# SKEMA_ALAT_UKUR-2025.net
KiCad netlist of a schematic drawn in EAGLE
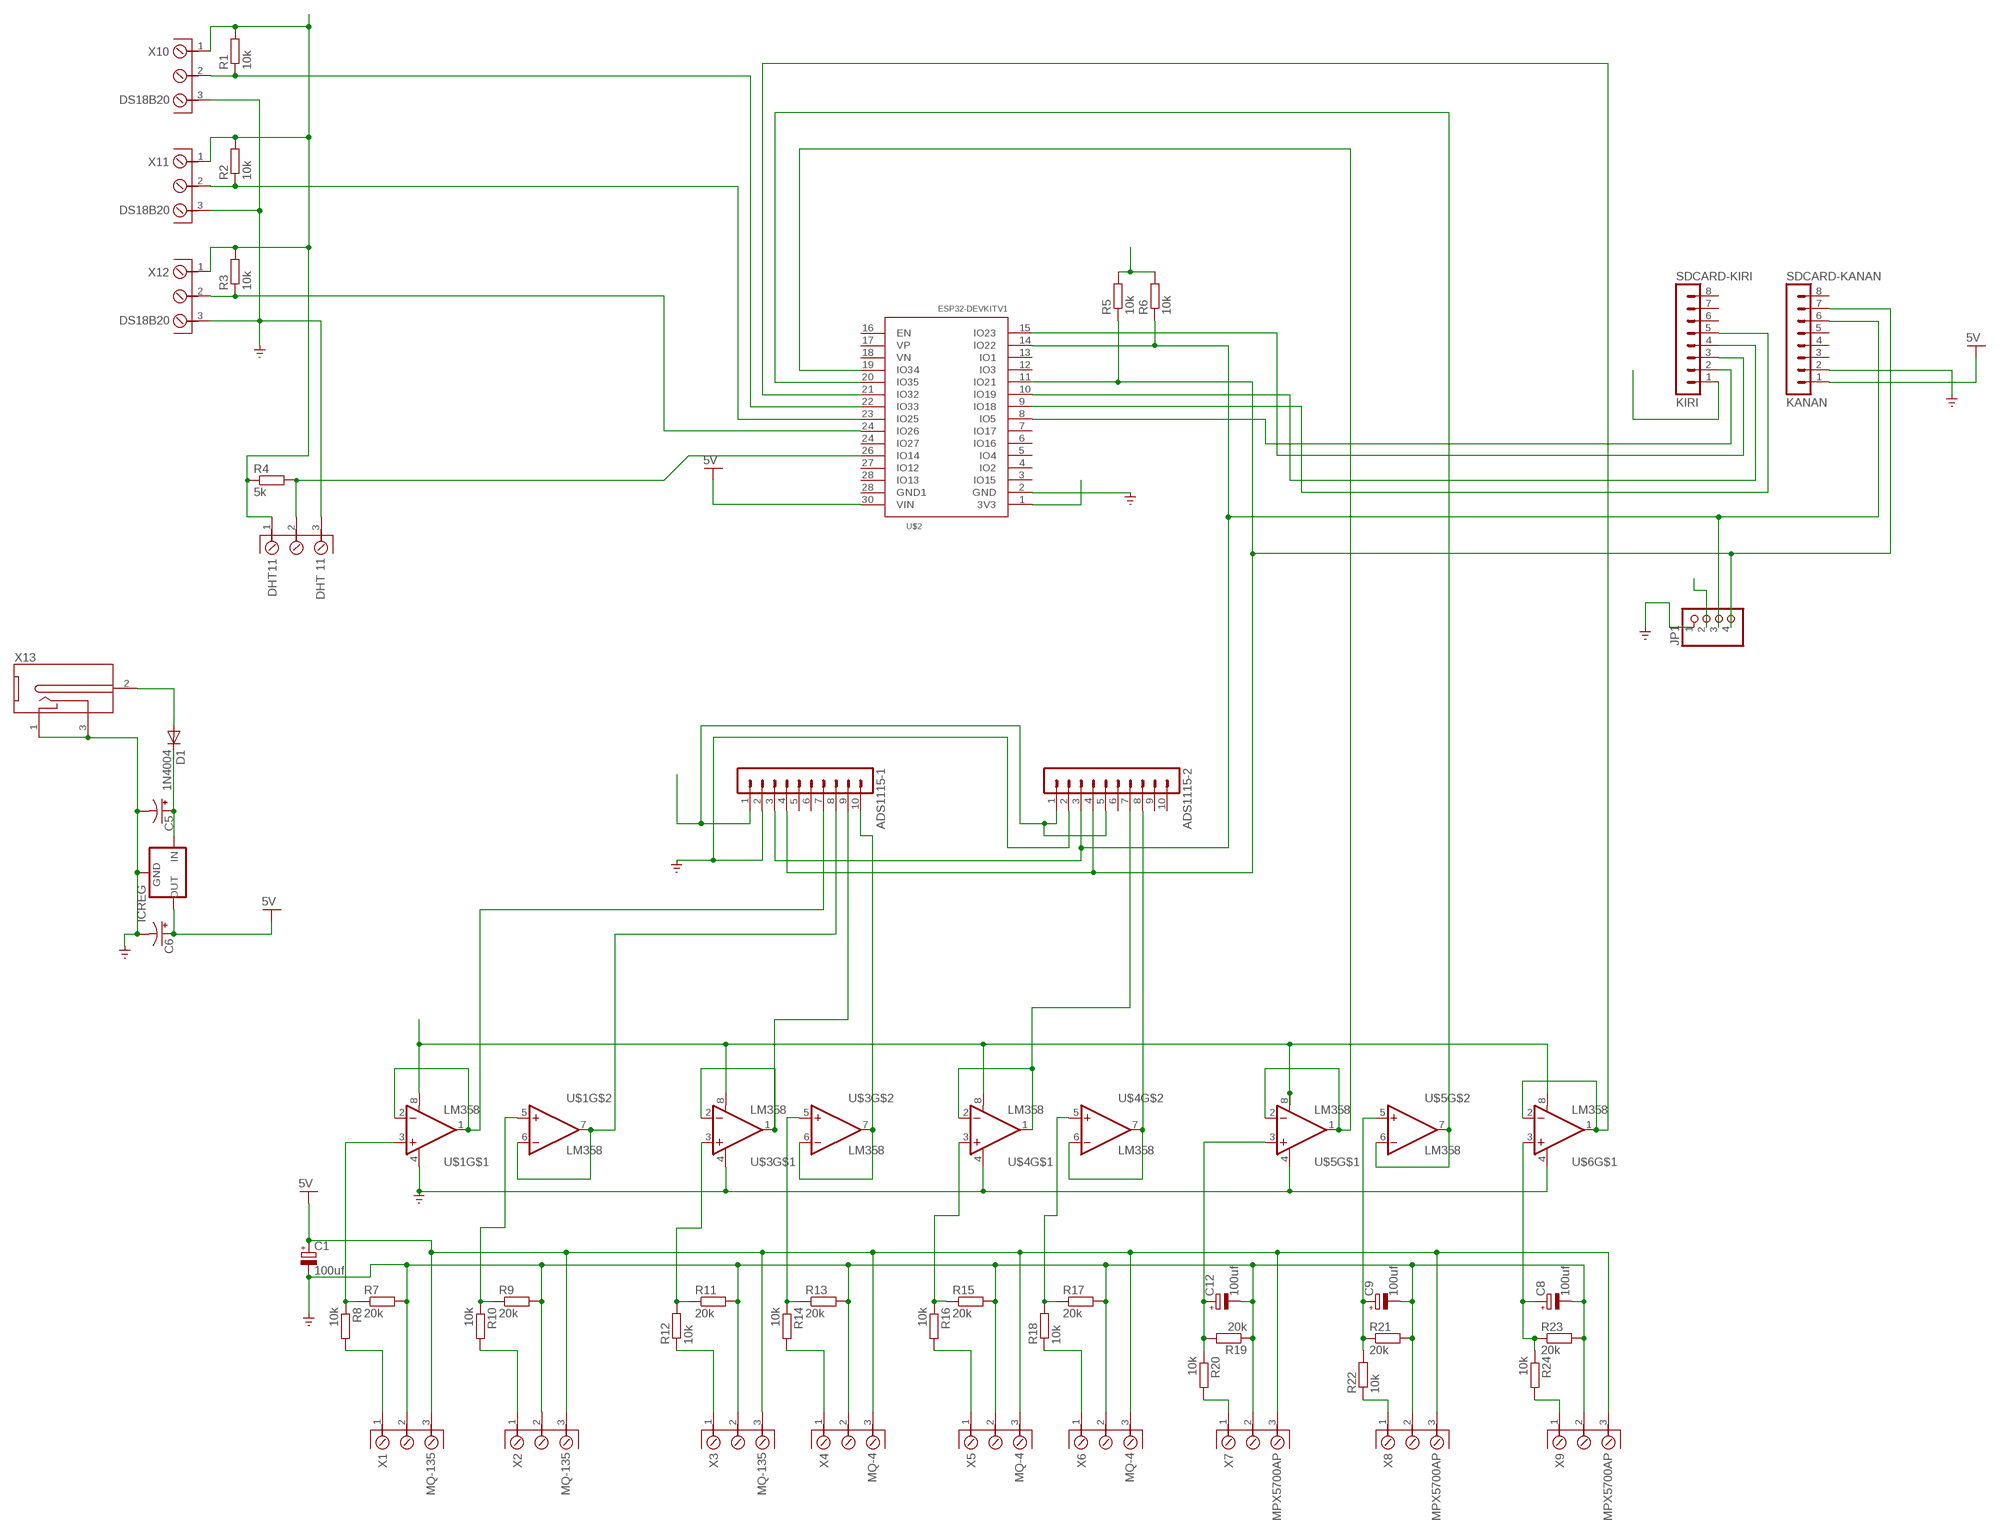
[diagram p0: schematic, sheet 1]

(export (version "E")
  (design (tool "Eeschema 10.0.6"))
  (components
    (comp (ref "ADS1115-1")
      (value "MA10-1")
      (footprint "eagle-import:MA10-1")
      (libsource (lib "eagle-import") (part "MA10-1"))
    )
    (comp (ref "ADS1115-2")
      (value "MA10-1")
      (footprint "eagle-import:MA10-1")
      (libsource (lib "eagle-import") (part "MA10-1"))
    )
    (comp (ref "C1")
      (value "100uf")
      (footprint "eagle-import:E5-10,5")
      (libsource (lib "eagle-import") (part "CPOL-EUE5-10.5"))
    )
    (comp (ref "C5")
      (value "CPOL-USE5-13")
      (footprint "eagle-import:E5-13")
      (libsource (lib "eagle-import") (part "CPOL-USE5-13"))
    )
    (comp (ref "C6")
      (value "CPOL-USE5-13")
      (footprint "eagle-import:E5-13")
      (libsource (lib "eagle-import") (part "CPOL-USE5-13"))
    )
    (comp (ref "C8")
      (value "100uf")
      (footprint "eagle-import:E5-10,5")
      (libsource (lib "eagle-import") (part "CPOL-EUE5-10.5"))
    )
    (comp (ref "C9")
      (value "100uf")
      (footprint "eagle-import:E5-10,5")
      (libsource (lib "eagle-import") (part "CPOL-EUE5-10.5"))
    )
    (comp (ref "C12")
      (value "100uf")
      (footprint "eagle-import:E5-10,5")
      (libsource (lib "eagle-import") (part "CPOL-EUE5-10.5"))
    )
    (comp (ref "D1")
      (value "1N4004")
      (footprint "eagle-import:DO41-10")
      (libsource (lib "eagle-import") (part "1N4004"))
    )
    (comp (ref "DHT11")
      (value "DHT 11")
      (footprint "eagle-import:AKL701_3_13")
      (libsource (lib "eagle-import") (part "AKL701_3_13"))
    )
    (comp (ref "ICREG")
      (value "78XXS")
      (footprint "eagle-import:78XXS")
      (libsource (lib "eagle-import") (part "78XXS"))
    )
    (comp (ref "JP1")
      (value "PINHD-1X4")
      (footprint "eagle-import:1X04")
      (libsource (lib "eagle-import") (part "PINHD-1X4"))
    )
    (comp (ref "R1")
      (value "10k")
      (footprint "eagle-import:0411_12")
      (libsource (lib "eagle-import") (part "R-EU_0411/12"))
    )
    (comp (ref "R2")
      (value "10k")
      (footprint "eagle-import:0411_12")
      (libsource (lib "eagle-import") (part "R-EU_0411/12"))
    )
    (comp (ref "R3")
      (value "10k")
      (footprint "eagle-import:0411_12")
      (libsource (lib "eagle-import") (part "R-EU_0411/12"))
    )
    (comp (ref "R4")
      (value "5k")
      (footprint "eagle-import:0411_12")
      (libsource (lib "eagle-import") (part "R-EU_0411/12"))
    )
    (comp (ref "R5")
      (value "10k")
      (footprint "eagle-import:0411_12")
      (libsource (lib "eagle-import") (part "R-EU_0411/12"))
    )
    (comp (ref "R6")
      (value "10k")
      (footprint "eagle-import:0411_12")
      (libsource (lib "eagle-import") (part "R-EU_0411/12"))
    )
    (comp (ref "R7")
      (value "20k")
      (footprint "eagle-import:0411_12")
      (libsource (lib "eagle-import") (part "R-EU_0411/12"))
    )
    (comp (ref "R8")
      (value "10k")
      (footprint "eagle-import:0411_12")
      (libsource (lib "eagle-import") (part "R-EU_0411/12"))
    )
    (comp (ref "R9")
      (value "20k")
      (footprint "eagle-import:0411_12")
      (libsource (lib "eagle-import") (part "R-EU_0411/12"))
    )
    (comp (ref "R10")
      (value "10k")
      (footprint "eagle-import:0411_12")
      (libsource (lib "eagle-import") (part "R-EU_0411/12"))
    )
    (comp (ref "R11")
      (value "20k")
      (footprint "eagle-import:0411_12")
      (libsource (lib "eagle-import") (part "R-EU_0411/12"))
    )
    (comp (ref "R12")
      (value "10k")
      (footprint "eagle-import:0411_12")
      (libsource (lib "eagle-import") (part "R-EU_0411/12"))
    )
    (comp (ref "R13")
      (value "20k")
      (footprint "eagle-import:0411_12")
      (libsource (lib "eagle-import") (part "R-EU_0411/12"))
    )
    (comp (ref "R14")
      (value "10k")
      (footprint "eagle-import:0411_12")
      (libsource (lib "eagle-import") (part "R-EU_0411/12"))
    )
    (comp (ref "R15")
      (value "20k")
      (footprint "eagle-import:0411_12")
      (libsource (lib "eagle-import") (part "R-EU_0411/12"))
    )
    (comp (ref "R16")
      (value "10k")
      (footprint "eagle-import:0411_12")
      (libsource (lib "eagle-import") (part "R-EU_0411/12"))
    )
    (comp (ref "R17")
      (value "20k")
      (footprint "eagle-import:0411_12")
      (libsource (lib "eagle-import") (part "R-EU_0411/12"))
    )
    (comp (ref "R18")
      (value "10k")
      (footprint "eagle-import:0411_12")
      (libsource (lib "eagle-import") (part "R-EU_0411/12"))
    )
    (comp (ref "R19")
      (value "20k")
      (footprint "eagle-import:0411_12")
      (libsource (lib "eagle-import") (part "R-EU_0411/12"))
    )
    (comp (ref "R20")
      (value "10k")
      (footprint "eagle-import:0411_12")
      (libsource (lib "eagle-import") (part "R-EU_0411/12"))
    )
    (comp (ref "R21")
      (value "20k")
      (footprint "eagle-import:0411_12")
      (libsource (lib "eagle-import") (part "R-EU_0411/12"))
    )
    (comp (ref "R22")
      (value "10k")
      (footprint "eagle-import:0411_12")
      (libsource (lib "eagle-import") (part "R-EU_0411/12"))
    )
    (comp (ref "R23")
      (value "20k")
      (footprint "eagle-import:0411_12")
      (libsource (lib "eagle-import") (part "R-EU_0411/12"))
    )
    (comp (ref "R24")
      (value "10k")
      (footprint "eagle-import:0411_12")
      (libsource (lib "eagle-import") (part "R-EU_0411/12"))
    )
    (comp (ref "SDCARD-KANAN")
      (value "KANAN")
      (footprint "eagle-import:MA08-1")
      (libsource (lib "eagle-import") (part "MA08-1"))
    )
    (comp (ref "SDCARD-KIRI")
      (value "KIRI")
      (footprint "eagle-import:MA08-1")
      (libsource (lib "eagle-import") (part "MA08-1"))
    )
    (comp (ref "U$1")
      (value "LM358")
      (footprint "eagle-import:DIP08")
      (libsource (lib "eagle-import") (part "LM358"))
    )
    (comp (ref "U$2")
      (value "ESP32DEVKITV1")
      (footprint "eagle-import:ESP32-DEVKITV1")
      (libsource (lib "eagle-import") (part "ESP32DEVKITV1"))
    )
    (comp (ref "U$3")
      (value "LM358")
      (footprint "eagle-import:DIP08")
      (libsource (lib "eagle-import") (part "LM358"))
    )
    (comp (ref "U$4")
      (value "LM358")
      (footprint "eagle-import:DIP08")
      (libsource (lib "eagle-import") (part "LM358"))
    )
    (comp (ref "U$5")
      (value "LM358")
      (footprint "eagle-import:DIP08")
      (libsource (lib "eagle-import") (part "LM358"))
    )
    (comp (ref "U$6")
      (value "LM358")
      (footprint "eagle-import:DIP08")
      (libsource (lib "eagle-import") (part "LM358"))
    )
    (comp (ref "X1")
      (value "MQ-135")
      (footprint "eagle-import:AKL701_3_13")
      (libsource (lib "eagle-import") (part "AKL701_3_13"))
    )
    (comp (ref "X2")
      (value "MQ-135")
      (footprint "eagle-import:AKL701_3_13")
      (libsource (lib "eagle-import") (part "AKL701_3_13"))
    )
    (comp (ref "X3")
      (value "MQ-135")
      (footprint "eagle-import:AKL701_3_13")
      (libsource (lib "eagle-import") (part "AKL701_3_13"))
    )
    (comp (ref "X4")
      (value "MQ-4")
      (footprint "eagle-import:AKL701_3_13")
      (libsource (lib "eagle-import") (part "AKL701_3_13"))
    )
    (comp (ref "X5")
      (value "MQ-4")
      (footprint "eagle-import:AKL701_3_13")
      (libsource (lib "eagle-import") (part "AKL701_3_13"))
    )
    (comp (ref "X6")
      (value "MQ-4")
      (footprint "eagle-import:AKL701_3_13")
      (libsource (lib "eagle-import") (part "AKL701_3_13"))
    )
    (comp (ref "X7")
      (value "MPX5700AP")
      (footprint "eagle-import:AKL701_3_13")
      (libsource (lib "eagle-import") (part "AKL701_3_13"))
    )
    (comp (ref "X8")
      (value "MPX5700AP")
      (footprint "eagle-import:AKL701_3_13")
      (libsource (lib "eagle-import") (part "AKL701_3_13"))
    )
    (comp (ref "X9")
      (value "MPX5700AP")
      (footprint "eagle-import:AKL701_3_13")
      (libsource (lib "eagle-import") (part "AKL701_3_13"))
    )
    (comp (ref "X10")
      (value "DS18B20")
      (footprint "eagle-import:AKL701_3_13")
      (libsource (lib "eagle-import") (part "AKL701_3_13"))
    )
    (comp (ref "X11")
      (value "DS18B20")
      (footprint "eagle-import:AKL701_3_13")
      (libsource (lib "eagle-import") (part "AKL701_3_13"))
    )
    (comp (ref "X12")
      (value "DS18B20")
      (footprint "eagle-import:AKL701_3_13")
      (libsource (lib "eagle-import") (part "AKL701_3_13"))
    )
    (comp (ref "X13")
      (value "DC-2.1MM-5MM")
      (footprint "eagle-import:DC-21MM")
      (libsource (lib "eagle-import") (part "DC-5MM-2.1MM"))
    )
  )
  (nets
    (net (code "1") (name "/3.3V") (class "Default")
      (node (ref "ADS1115-1") (pin "1") (pinfunction "1_1") (pintype "passive"))
      (node (ref "ADS1115-2") (pin "1") (pinfunction "1_1") (pintype "passive"))
      (node (ref "ADS1115-2") (pin "5") (pinfunction "5_5") (pintype "passive"))
      (node (ref "DHT11") (pin "1") (pinfunction "1_1") (pintype "passive"))
      (node (ref "JP1") (pin "2") (pinfunction "2_2") (pintype "passive"))
      (node (ref "R1") (pin "2") (pinfunction "2_2") (pintype "passive"))
      (node (ref "R2") (pin "2") (pinfunction "2_2") (pintype "passive"))
      (node (ref "R3") (pin "2") (pinfunction "2_2") (pintype "passive"))
      (node (ref "R4") (pin "1") (pinfunction "1_1") (pintype "passive"))
      (node (ref "R5") (pin "2") (pinfunction "2_2") (pintype "passive"))
      (node (ref "R6") (pin "2") (pinfunction "2_2") (pintype "passive"))
      (node (ref "SDCARD-KIRI") (pin "1") (pinfunction "1_1") (pintype "passive"))
      (node (ref "U$1") (pin "8") (pinfunction "V+_8") (pintype "power_in"))
      (node (ref "U$2") (pin "1") (pinfunction "3V3_1") (pintype "bidirectional"))
      (node (ref "U$3") (pin "8") (pinfunction "V+_8") (pintype "power_in"))
      (node (ref "U$4") (pin "8") (pinfunction "V+_8") (pintype "power_in"))
      (node (ref "U$5") (pin "8") (pinfunction "V+_8") (pintype "power_in"))
      (node (ref "U$6") (pin "8") (pinfunction "V+_8") (pintype "power_in"))
      (node (ref "X10") (pin "1") (pinfunction "1_1") (pintype "passive"))
      (node (ref "X11") (pin "1") (pinfunction "1_1") (pintype "passive"))
      (node (ref "X12") (pin "1") (pinfunction "1_1") (pintype "passive"))
    )
    (net (code "2") (name "5V") (class "Default")
      (node (ref "C1") (pin "+") (pinfunction "+_+") (pintype "passive"))
      (node (ref "C6") (pin "+") (pinfunction "+_+") (pintype "passive"))
      (node (ref "ICREG") (pin "OUT") (pinfunction "OUT_OUT") (pintype "passive"))
      (node (ref "SDCARD-KANAN") (pin "1") (pinfunction "1_1") (pintype "passive"))
      (node (ref "U$2") (pin "30") (pinfunction "VIN_30") (pintype "bidirectional"))
      (node (ref "X1") (pin "3") (pinfunction "3_3") (pintype "passive"))
      (node (ref "X2") (pin "3") (pinfunction "3_3") (pintype "passive"))
      (node (ref "X3") (pin "3") (pinfunction "3_3") (pintype "passive"))
      (node (ref "X4") (pin "3") (pinfunction "3_3") (pintype "passive"))
      (node (ref "X5") (pin "3") (pinfunction "3_3") (pintype "passive"))
      (node (ref "X6") (pin "3") (pinfunction "3_3") (pintype "passive"))
      (node (ref "X7") (pin "3") (pinfunction "3_3") (pintype "passive"))
      (node (ref "X8") (pin "3") (pinfunction "3_3") (pintype "passive"))
      (node (ref "X9") (pin "3") (pinfunction "3_3") (pintype "passive"))
    )
    (net (code "3") (name "GND_") (class "Default")
      (node (ref "ADS1115-1") (pin "2") (pinfunction "2_2") (pintype "passive"))
      (node (ref "ADS1115-2") (pin "2") (pinfunction "2_2") (pintype "passive"))
      (node (ref "C1") (pin "-") (pinfunction "-_-") (pintype "passive"))
      (node (ref "C12") (pin "-") (pinfunction "-_-") (pintype "passive"))
      (node (ref "C5") (pin "-") (pinfunction "-_-") (pintype "passive"))
      (node (ref "C6") (pin "-") (pinfunction "-_-") (pintype "passive"))
      (node (ref "C8") (pin "-") (pinfunction "-_-") (pintype "passive"))
      (node (ref "C9") (pin "-") (pinfunction "-_-") (pintype "passive"))
      (node (ref "DHT11") (pin "3") (pinfunction "3_3") (pintype "passive"))
      (node (ref "ICREG") (pin "GND") (pinfunction "GND_GND") (pintype "input"))
      (node (ref "JP1") (pin "1") (pinfunction "1_1") (pintype "passive"))
      (node (ref "R11") (pin "2") (pinfunction "2_2") (pintype "passive"))
      (node (ref "R13") (pin "2") (pinfunction "2_2") (pintype "passive"))
      (node (ref "R15") (pin "2") (pinfunction "2_2") (pintype "passive"))
      (node (ref "R17") (pin "2") (pinfunction "2_2") (pintype "passive"))
      (node (ref "R19") (pin "1") (pinfunction "1_1") (pintype "passive"))
      (node (ref "R21") (pin "2") (pinfunction "2_2") (pintype "passive"))
      (node (ref "R23") (pin "2") (pinfunction "2_2") (pintype "passive"))
      (node (ref "R7") (pin "2") (pinfunction "2_2") (pintype "passive"))
      (node (ref "R9") (pin "2") (pinfunction "2_2") (pintype "passive"))
      (node (ref "SDCARD-KANAN") (pin "2") (pinfunction "2_2") (pintype "passive"))
      (node (ref "U$1") (pin "4") (pinfunction "V-_4") (pintype "power_in"))
      (node (ref "U$2") (pin "2") (pinfunction "GND_2") (pintype "bidirectional"))
      (node (ref "U$3") (pin "4") (pinfunction "V-_4") (pintype "power_in"))
      (node (ref "U$4") (pin "4") (pinfunction "V-_4") (pintype "power_in"))
      (node (ref "U$5") (pin "4") (pinfunction "V-_4") (pintype "power_in"))
      (node (ref "U$6") (pin "4") (pinfunction "V-_4") (pintype "power_in"))
      (node (ref "X1") (pin "2") (pinfunction "2_2") (pintype "passive"))
      (node (ref "X10") (pin "3") (pinfunction "3_3") (pintype "passive"))
      (node (ref "X11") (pin "3") (pinfunction "3_3") (pintype "passive"))
      (node (ref "X12") (pin "3") (pinfunction "3_3") (pintype "passive"))
      (node (ref "X13") (pin "1") (pinfunction "1_1") (pintype "power_in"))
      (node (ref "X13") (pin "3") (pinfunction "2_3") (pintype "power_in"))
      (node (ref "X2") (pin "2") (pinfunction "2_2") (pintype "passive"))
      (node (ref "X3") (pin "2") (pinfunction "2_2") (pintype "passive"))
      (node (ref "X4") (pin "2") (pinfunction "2_2") (pintype "passive"))
      (node (ref "X5") (pin "2") (pinfunction "2_2") (pintype "passive"))
      (node (ref "X6") (pin "2") (pinfunction "2_2") (pintype "passive"))
      (node (ref "X7") (pin "2") (pinfunction "2_2") (pintype "passive"))
      (node (ref "X8") (pin "2") (pinfunction "2_2") (pintype "passive"))
      (node (ref "X9") (pin "2") (pinfunction "2_2") (pintype "passive"))
    )
    (net (code "4") (name "Net-(C5-Pad+)") (class "Default")
      (node (ref "C5") (pin "+") (pinfunction "+_+") (pintype "passive"))
      (node (ref "D1") (pin "C") (pinfunction "C_C") (pintype "passive"))
      (node (ref "ICREG") (pin "IN") (pinfunction "IN_IN") (pintype "input"))
    )
    (net (code "5") (name "Net-(R8-Pad2)") (class "Default")
      (node (ref "R8") (pin "2") (pinfunction "2_2") (pintype "passive"))
      (node (ref "X1") (pin "1") (pinfunction "1_1") (pintype "passive"))
    )
    (net (code "6") (name "Net-(R10-Pad2)") (class "Default")
      (node (ref "R10") (pin "2") (pinfunction "2_2") (pintype "passive"))
      (node (ref "X2") (pin "1") (pinfunction "1_1") (pintype "passive"))
    )
    (net (code "7") (name "Net-(R12-Pad1)") (class "Default")
      (node (ref "R12") (pin "1") (pinfunction "1_1") (pintype "passive"))
      (node (ref "X3") (pin "1") (pinfunction "1_1") (pintype "passive"))
    )
    (net (code "8") (name "Net-(R14-Pad2)") (class "Default")
      (node (ref "R14") (pin "2") (pinfunction "2_2") (pintype "passive"))
      (node (ref "X4") (pin "1") (pinfunction "1_1") (pintype "passive"))
    )
    (net (code "9") (name "Net-(R16-Pad2)") (class "Default")
      (node (ref "R16") (pin "2") (pinfunction "2_2") (pintype "passive"))
      (node (ref "X5") (pin "1") (pinfunction "1_1") (pintype "passive"))
    )
    (net (code "10") (name "Net-(R18-Pad1)") (class "Default")
      (node (ref "R18") (pin "1") (pinfunction "1_1") (pintype "passive"))
      (node (ref "X6") (pin "1") (pinfunction "1_1") (pintype "passive"))
    )
    (net (code "11") (name "Net-(R20-Pad2)") (class "Default")
      (node (ref "R20") (pin "2") (pinfunction "2_2") (pintype "passive"))
      (node (ref "X7") (pin "1") (pinfunction "1_1") (pintype "passive"))
    )
    (net (code "12") (name "Net-(R22-Pad1)") (class "Default")
      (node (ref "R22") (pin "1") (pinfunction "1_1") (pintype "passive"))
      (node (ref "X8") (pin "1") (pinfunction "1_1") (pintype "passive"))
    )
    (net (code "13") (name "Net-(R24-Pad2)") (class "Default")
      (node (ref "R24") (pin "2") (pinfunction "2_2") (pintype "passive"))
      (node (ref "X9") (pin "1") (pinfunction "1_1") (pintype "passive"))
    )
    (net (code "14") (name "Net-(U$1A-+IN)") (class "Default")
      (node (ref "R7") (pin "1") (pinfunction "1_1") (pintype "passive"))
      (node (ref "R8") (pin "1") (pinfunction "1_1") (pintype "passive"))
      (node (ref "U$1") (pin "3") (pinfunction "+IN_3") (pintype "input"))
    )
    (net (code "15") (name "Net-(U$1A--IN)") (class "Default")
      (node (ref "ADS1115-1") (pin "7") (pinfunction "7_7") (pintype "passive"))
      (node (ref "U$1") (pin "1") (pinfunction "OUT_1") (pintype "output"))
      (node (ref "U$1") (pin "2") (pinfunction "-IN_2") (pintype "input"))
    )
    (net (code "16") (name "Net-(U$1B-+IN)") (class "Default")
      (node (ref "R10") (pin "1") (pinfunction "1_1") (pintype "passive"))
      (node (ref "R9") (pin "1") (pinfunction "1_1") (pintype "passive"))
      (node (ref "U$1") (pin "5") (pinfunction "+IN_5") (pintype "input"))
    )
    (net (code "17") (name "Net-(U$1B--IN)") (class "Default")
      (node (ref "ADS1115-1") (pin "8") (pinfunction "8_8") (pintype "passive"))
      (node (ref "U$1") (pin "6") (pinfunction "-IN_6") (pintype "input"))
      (node (ref "U$1") (pin "7") (pinfunction "OUT_7") (pintype "output"))
    )
    (net (code "18") (name "Net-(U$2-IO5)") (class "Default")
      (node (ref "SDCARD-KIRI") (pin "2") (pinfunction "2_2") (pintype "passive"))
      (node (ref "U$2") (pin "8") (pinfunction "IO5_8") (pintype "bidirectional"))
    )
    (net (code "19") (name "Net-(U$2-IO14)") (class "Default")
      (node (ref "DHT11") (pin "2") (pinfunction "2_2") (pintype "passive"))
      (node (ref "R4") (pin "2") (pinfunction "2_2") (pintype "passive"))
      (node (ref "U$2") (pin "26") (pinfunction "IO14_26") (pintype "bidirectional"))
    )
    (net (code "20") (name "Net-(U$2-IO18)") (class "Default")
      (node (ref "SDCARD-KIRI") (pin "5") (pinfunction "5_5") (pintype "passive"))
      (node (ref "U$2") (pin "9") (pinfunction "IO18_9") (pintype "bidirectional"))
    )
    (net (code "21") (name "Net-(U$2-IO19)") (class "Default")
      (node (ref "SDCARD-KIRI") (pin "4") (pinfunction "4_4") (pintype "passive"))
      (node (ref "U$2") (pin "10") (pinfunction "IO19_10") (pintype "bidirectional"))
    )
    (net (code "22") (name "Net-(U$2-IO21)") (class "Default")
      (node (ref "ADS1115-1") (pin "4") (pinfunction "4_4") (pintype "passive"))
      (node (ref "ADS1115-2") (pin "4") (pinfunction "4_4") (pintype "passive"))
      (node (ref "JP1") (pin "4") (pinfunction "4_4") (pintype "passive"))
      (node (ref "R5") (pin "1") (pinfunction "1_1") (pintype "passive"))
      (node (ref "SDCARD-KANAN") (pin "7") (pinfunction "7_7") (pintype "passive"))
      (node (ref "U$2") (pin "11") (pinfunction "IO21_11") (pintype "bidirectional"))
    )
    (net (code "23") (name "Net-(U$2-IO22)") (class "Default")
      (node (ref "ADS1115-1") (pin "3") (pinfunction "3_3") (pintype "passive"))
      (node (ref "ADS1115-2") (pin "3") (pinfunction "3_3") (pintype "passive"))
      (node (ref "JP1") (pin "3") (pinfunction "3_3") (pintype "passive"))
      (node (ref "R6") (pin "1") (pinfunction "1_1") (pintype "passive"))
      (node (ref "SDCARD-KANAN") (pin "6") (pinfunction "6_6") (pintype "passive"))
      (node (ref "U$2") (pin "14") (pinfunction "IO22_14") (pintype "bidirectional"))
    )
    (net (code "24") (name "Net-(U$2-IO23)") (class "Default")
      (node (ref "SDCARD-KIRI") (pin "3") (pinfunction "3_3") (pintype "passive"))
      (node (ref "U$2") (pin "15") (pinfunction "IO23_15") (pintype "bidirectional"))
    )
    (net (code "25") (name "Net-(U$2-IO25)") (class "Default")
      (node (ref "R2") (pin "1") (pinfunction "1_1") (pintype "passive"))
      (node (ref "U$2") (pin "23") (pinfunction "IO25_23") (pintype "bidirectional"))
      (node (ref "X11") (pin "2") (pinfunction "2_2") (pintype "passive"))
    )
    (net (code "26") (name "Net-(U$2-IO26)") (class "Default")
      (node (ref "R3") (pin "1") (pinfunction "1_1") (pintype "passive"))
      (node (ref "U$2") (pin "24") (pinfunction "IO26_24") (pintype "bidirectional"))
      (node (ref "X12") (pin "2") (pinfunction "2_2") (pintype "passive"))
    )
    (net (code "27") (name "Net-(U$2-IO32)") (class "Default")
      (node (ref "U$2") (pin "21") (pinfunction "IO32_21") (pintype "bidirectional"))
      (node (ref "U$6") (pin "1") (pinfunction "OUT_1") (pintype "output"))
      (node (ref "U$6") (pin "2") (pinfunction "-IN_2") (pintype "input"))
    )
    (net (code "28") (name "Net-(U$2-IO33)") (class "Default")
      (node (ref "R1") (pin "1") (pinfunction "1_1") (pintype "passive"))
      (node (ref "U$2") (pin "22") (pinfunction "IO33_22") (pintype "bidirectional"))
      (node (ref "X10") (pin "2") (pinfunction "2_2") (pintype "passive"))
    )
    (net (code "29") (name "Net-(U$2-IO34)") (class "Default")
      (node (ref "U$2") (pin "19") (pinfunction "IO34_19") (pintype "bidirectional"))
      (node (ref "U$5") (pin "1") (pinfunction "OUT_1") (pintype "output"))
      (node (ref "U$5") (pin "2") (pinfunction "-IN_2") (pintype "input"))
    )
    (net (code "30") (name "Net-(U$2-IO35)") (class "Default")
      (node (ref "U$2") (pin "20") (pinfunction "IO35_20") (pintype "bidirectional"))
      (node (ref "U$5") (pin "6") (pinfunction "-IN_6") (pintype "input"))
      (node (ref "U$5") (pin "7") (pinfunction "OUT_7") (pintype "output"))
    )
    (net (code "31") (name "Net-(U$3A-+IN)") (class "Default")
      (node (ref "R11") (pin "1") (pinfunction "1_1") (pintype "passive"))
      (node (ref "R12") (pin "2") (pinfunction "2_2") (pintype "passive"))
      (node (ref "U$3") (pin "3") (pinfunction "+IN_3") (pintype "input"))
    )
    (net (code "32") (name "Net-(U$3A--IN)") (class "Default")
      (node (ref "ADS1115-1") (pin "9") (pinfunction "9_9") (pintype "passive"))
      (node (ref "U$3") (pin "1") (pinfunction "OUT_1") (pintype "output"))
      (node (ref "U$3") (pin "2") (pinfunction "-IN_2") (pintype "input"))
    )
    (net (code "33") (name "Net-(U$3B-+IN)") (class "Default")
      (node (ref "R13") (pin "1") (pinfunction "1_1") (pintype "passive"))
      (node (ref "R14") (pin "1") (pinfunction "1_1") (pintype "passive"))
      (node (ref "U$3") (pin "5") (pinfunction "+IN_5") (pintype "input"))
    )
    (net (code "34") (name "Net-(U$3B--IN)") (class "Default")
      (node (ref "ADS1115-1") (pin "10") (pinfunction "10_10") (pintype "passive"))
      (node (ref "U$3") (pin "6") (pinfunction "-IN_6") (pintype "input"))
      (node (ref "U$3") (pin "7") (pinfunction "OUT_7") (pintype "output"))
    )
    (net (code "35") (name "Net-(U$4A-+IN)") (class "Default")
      (node (ref "R15") (pin "1") (pinfunction "1_1") (pintype "passive"))
      (node (ref "R16") (pin "1") (pinfunction "1_1") (pintype "passive"))
      (node (ref "U$4") (pin "3") (pinfunction "+IN_3") (pintype "input"))
    )
    (net (code "36") (name "Net-(U$4A--IN)") (class "Default")
      (node (ref "ADS1115-2") (pin "7") (pinfunction "7_7") (pintype "passive"))
      (node (ref "U$4") (pin "1") (pinfunction "OUT_1") (pintype "output"))
      (node (ref "U$4") (pin "2") (pinfunction "-IN_2") (pintype "input"))
    )
    (net (code "37") (name "Net-(U$4B-+IN)") (class "Default")
      (node (ref "R17") (pin "1") (pinfunction "1_1") (pintype "passive"))
      (node (ref "R18") (pin "2") (pinfunction "2_2") (pintype "passive"))
      (node (ref "U$4") (pin "5") (pinfunction "+IN_5") (pintype "input"))
    )
    (net (code "38") (name "Net-(U$4B--IN)") (class "Default")
      (node (ref "ADS1115-2") (pin "8") (pinfunction "8_8") (pintype "passive"))
      (node (ref "U$4") (pin "6") (pinfunction "-IN_6") (pintype "input"))
      (node (ref "U$4") (pin "7") (pinfunction "OUT_7") (pintype "output"))
    )
    (net (code "39") (name "Net-(U$5A-+IN)") (class "Default")
      (node (ref "C12") (pin "+") (pinfunction "+_+") (pintype "passive"))
      (node (ref "R19") (pin "2") (pinfunction "2_2") (pintype "passive"))
      (node (ref "R20") (pin "1") (pinfunction "1_1") (pintype "passive"))
      (node (ref "U$5") (pin "3") (pinfunction "+IN_3") (pintype "input"))
    )
    (net (code "40") (name "Net-(U$5B-+IN)") (class "Default")
      (node (ref "C9") (pin "+") (pinfunction "+_+") (pintype "passive"))
      (node (ref "R21") (pin "1") (pinfunction "1_1") (pintype "passive"))
      (node (ref "R22") (pin "2") (pinfunction "2_2") (pintype "passive"))
      (node (ref "U$5") (pin "5") (pinfunction "+IN_5") (pintype "input"))
    )
    (net (code "41") (name "Net-(U$6A-+IN)") (class "Default")
      (node (ref "C8") (pin "+") (pinfunction "+_+") (pintype "passive"))
      (node (ref "R23") (pin "1") (pinfunction "1_1") (pintype "passive"))
      (node (ref "R24") (pin "1") (pinfunction "1_1") (pintype "passive"))
      (node (ref "U$6") (pin "3") (pinfunction "+IN_3") (pintype "input"))
    )
    (net (code "42") (name "Net-(X13-3)") (class "Default")
      (node (ref "D1") (pin "A") (pinfunction "A_A") (pintype "passive"))
      (node (ref "X13") (pin "2") (pinfunction "3_2") (pintype "power_in"))
    )
    (net (code "43") (name "unconnected-(ADS1115-1-Pad5)") (class "Default")
      (node (ref "ADS1115-1") (pin "5") (pinfunction "5_5") (pintype "passive"))
    )
    (net (code "44") (name "unconnected-(ADS1115-1-Pad6)") (class "Default")
      (node (ref "ADS1115-1") (pin "6") (pinfunction "6_6") (pintype "passive"))
    )
    (net (code "45") (name "unconnected-(ADS1115-2-Pad6)") (class "Default")
      (node (ref "ADS1115-2") (pin "6") (pinfunction "6_6") (pintype "passive"))
    )
    (net (code "46") (name "unconnected-(ADS1115-2-Pad9)") (class "Default")
      (node (ref "ADS1115-2") (pin "9") (pinfunction "9_9") (pintype "passive"))
    )
    (net (code "47") (name "unconnected-(ADS1115-2-Pad10)") (class "Default")
      (node (ref "ADS1115-2") (pin "10") (pinfunction "10_10") (pintype "passive"))
    )
    (net (code "48") (name "unconnected-(SDCARD-KANAN-Pad3)") (class "Default")
      (node (ref "SDCARD-KANAN") (pin "3") (pinfunction "3_3") (pintype "passive"))
    )
    (net (code "49") (name "unconnected-(SDCARD-KANAN-Pad4)") (class "Default")
      (node (ref "SDCARD-KANAN") (pin "4") (pinfunction "4_4") (pintype "passive"))
    )
    (net (code "50") (name "unconnected-(SDCARD-KANAN-Pad5)") (class "Default")
      (node (ref "SDCARD-KANAN") (pin "5") (pinfunction "5_5") (pintype "passive"))
    )
    (net (code "51") (name "unconnected-(SDCARD-KANAN-Pad8)") (class "Default")
      (node (ref "SDCARD-KANAN") (pin "8") (pinfunction "8_8") (pintype "passive"))
    )
    (net (code "52") (name "unconnected-(SDCARD-KIRI-Pad6)") (class "Default")
      (node (ref "SDCARD-KIRI") (pin "6") (pinfunction "6_6") (pintype "passive"))
    )
    (net (code "53") (name "unconnected-(SDCARD-KIRI-Pad7)") (class "Default")
      (node (ref "SDCARD-KIRI") (pin "7") (pinfunction "7_7") (pintype "passive"))
    )
    (net (code "54") (name "unconnected-(SDCARD-KIRI-Pad8)") (class "Default")
      (node (ref "SDCARD-KIRI") (pin "8") (pinfunction "8_8") (pintype "passive"))
    )
    (net (code "55") (name "unconnected-(U$2-EN-Pad16)") (class "Default")
      (node (ref "U$2") (pin "16") (pinfunction "EN_16") (pintype "bidirectional"))
    )
    (net (code "56") (name "unconnected-(U$2-GND1-Pad28)") (class "Default")
      (node (ref "U$2") (pin "28") (pinfunction "GND1_28") (pintype "bidirectional"))
    )
    (net (code "57") (name "unconnected-(U$2-IO1-Pad13)") (class "Default")
      (node (ref "U$2") (pin "13") (pinfunction "IO1_13") (pintype "bidirectional"))
    )
    (net (code "58") (name "unconnected-(U$2-IO2-Pad4)") (class "Default")
      (node (ref "U$2") (pin "4") (pinfunction "IO2_4") (pintype "bidirectional"))
    )
    (net (code "59") (name "unconnected-(U$2-IO3-Pad12)") (class "Default")
      (node (ref "U$2") (pin "12") (pinfunction "IO3_12") (pintype "bidirectional"))
    )
    (net (code "60") (name "unconnected-(U$2-IO4-Pad5)") (class "Default")
      (node (ref "U$2") (pin "5") (pinfunction "IO4_5") (pintype "bidirectional"))
    )
    (net (code "61") (name "unconnected-(U$2-IO12-Pad27)") (class "Default")
      (node (ref "U$2") (pin "27") (pinfunction "IO12_27") (pintype "bidirectional"))
    )
    (net (code "62") (name "unconnected-(U$2-IO13-Pad28)") (class "Default")
      (node (ref "U$2") (pin "28") (pinfunction "IO13_28") (pintype "bidirectional"))
    )
    (net (code "63") (name "unconnected-(U$2-IO15-Pad3)") (class "Default")
      (node (ref "U$2") (pin "3") (pinfunction "IO15_3") (pintype "bidirectional"))
    )
    (net (code "64") (name "unconnected-(U$2-IO16-Pad6)") (class "Default")
      (node (ref "U$2") (pin "6") (pinfunction "IO16_6") (pintype "bidirectional"))
    )
    (net (code "65") (name "unconnected-(U$2-IO17-Pad7)") (class "Default")
      (node (ref "U$2") (pin "7") (pinfunction "IO17_7") (pintype "bidirectional"))
    )
    (net (code "66") (name "unconnected-(U$2-IO27-Pad24)") (class "Default")
      (node (ref "U$2") (pin "24") (pinfunction "IO27_24") (pintype "bidirectional"))
    )
    (net (code "67") (name "unconnected-(U$2-VN-Pad18)") (class "Default")
      (node (ref "U$2") (pin "18") (pinfunction "VN_18") (pintype "bidirectional"))
    )
    (net (code "68") (name "unconnected-(U$2-VP-Pad17)") (class "Default")
      (node (ref "U$2") (pin "17") (pinfunction "VP_17") (pintype "bidirectional"))
    )
  )
)
